# DM1092_USB.net
KiCad netlist of a schematic drawn in Altium Designer
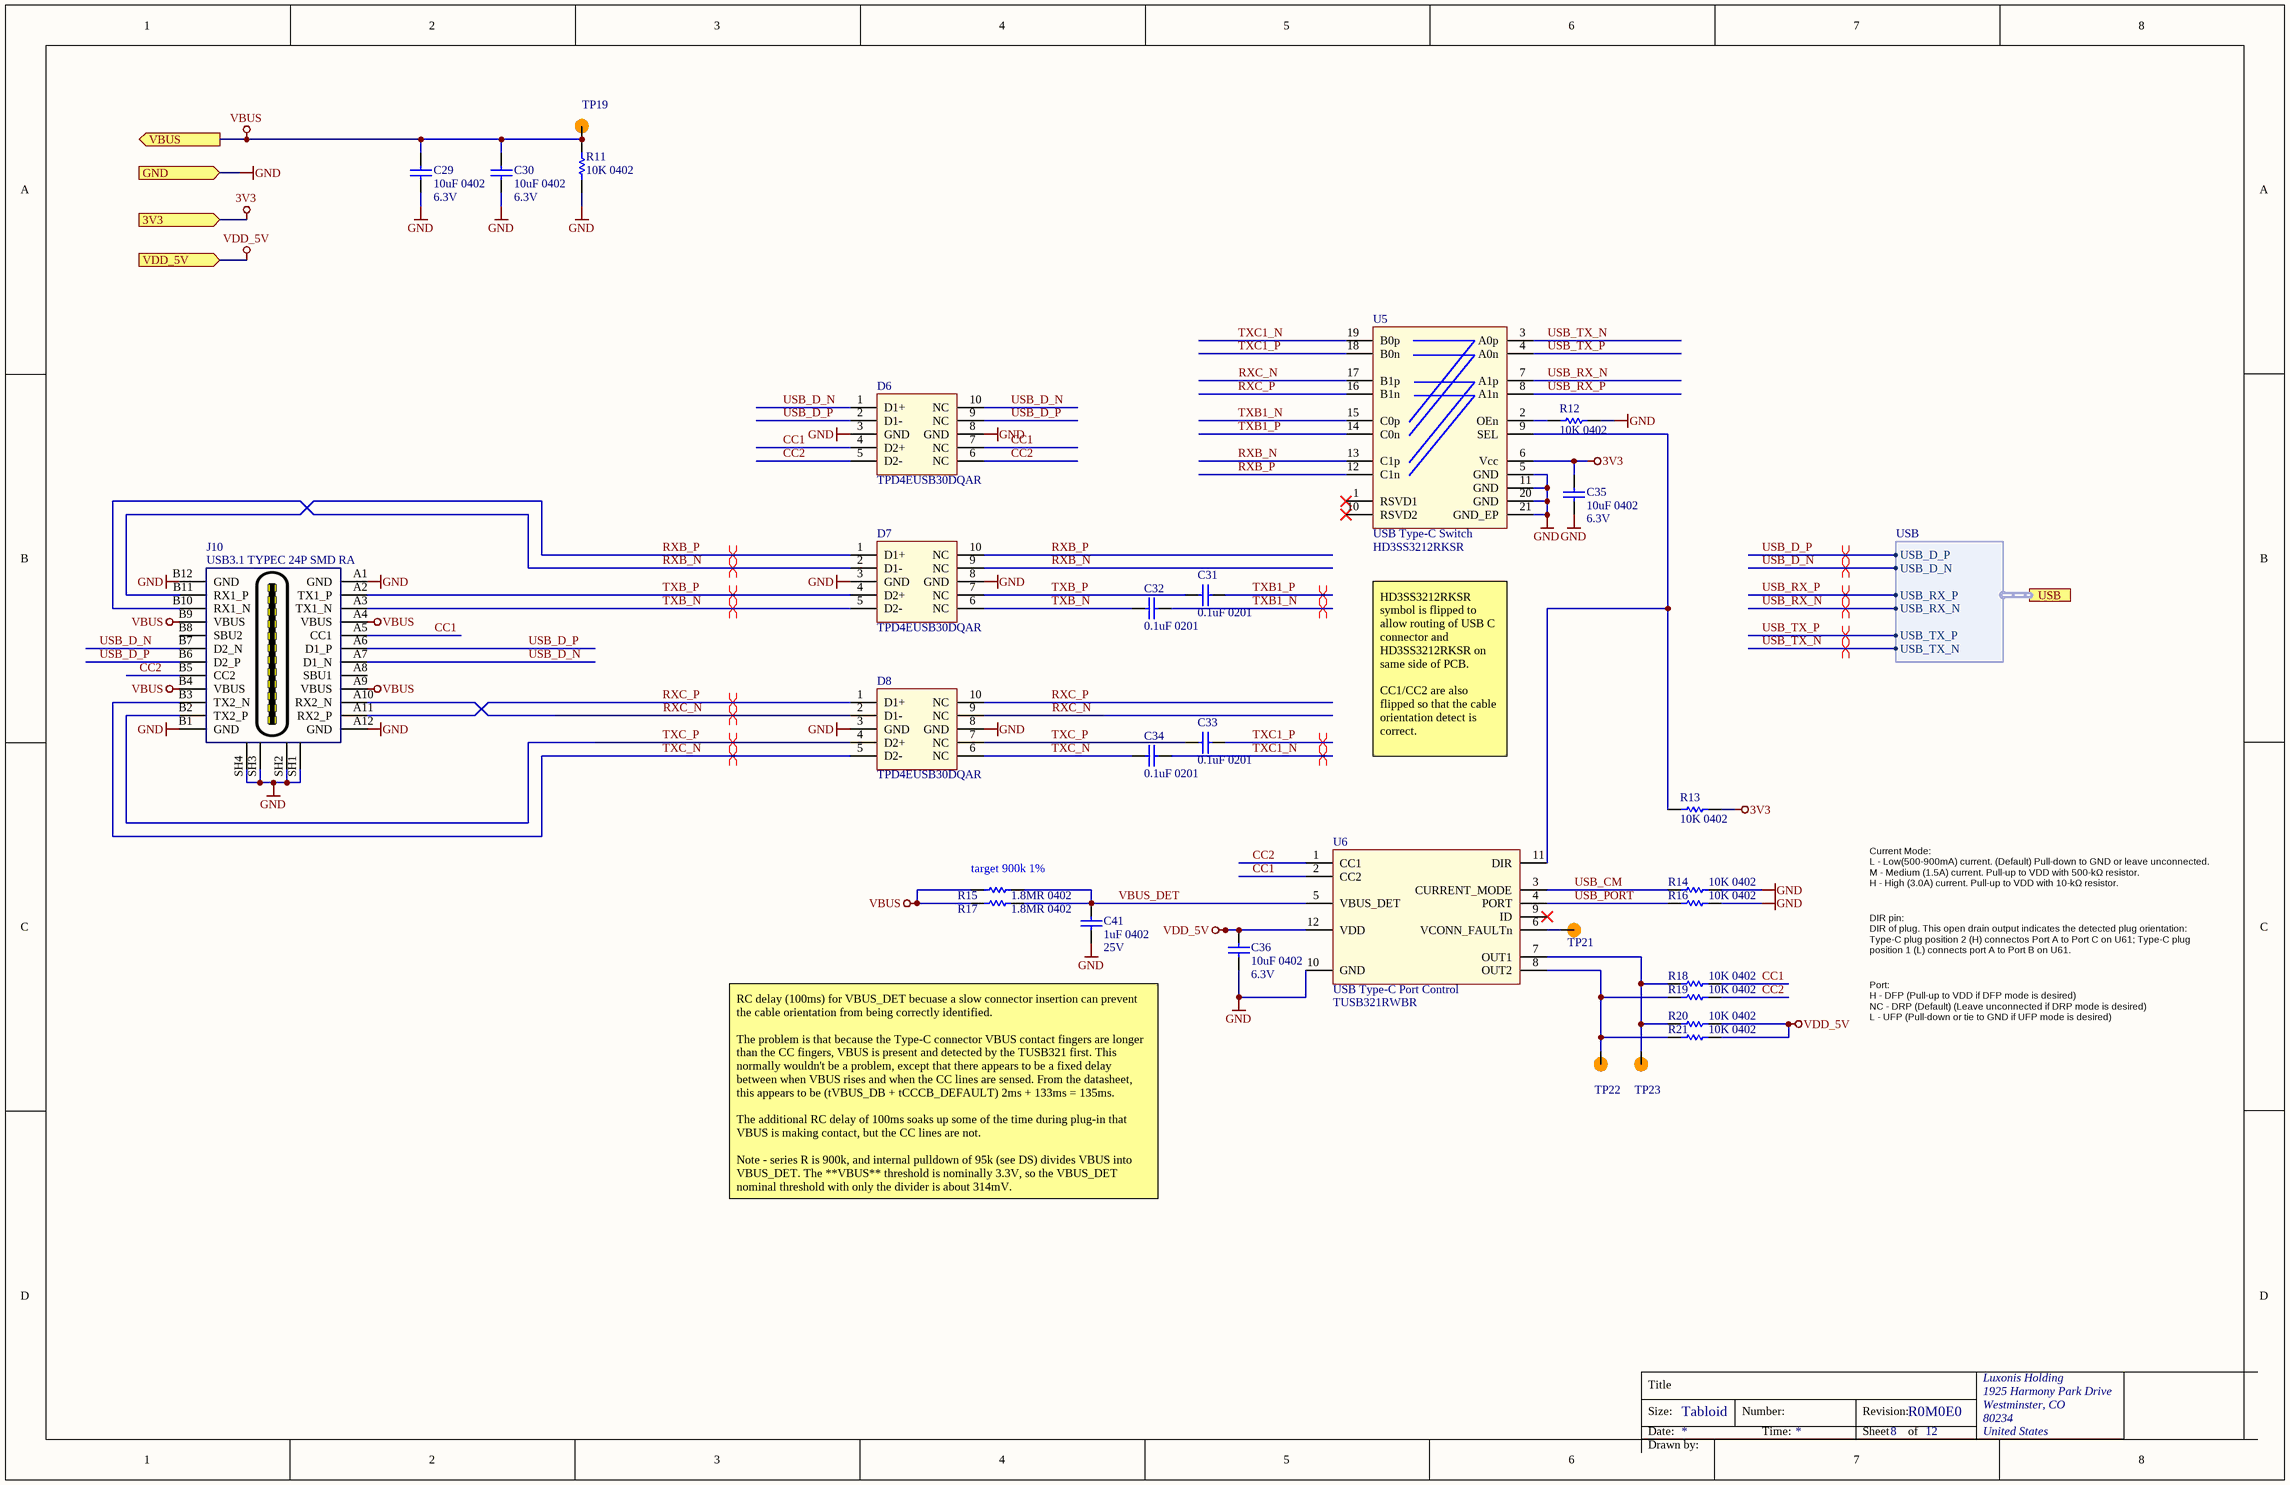
[diagram p0: DM1092_USB.SchDoc]

(export (version "E")
  (design (tool "Eeschema 10.0.6"))
  (components
    (comp (ref "C29")
      (value "10uF 0402")
      (footprint "CAP_Altium_Vault_Generic:CAPC0402(1005)70_L")
      (description "CAP CER 10UF 6.3V X5R 0402 20%")
      (fields (field (name "TOLERANCE") "20%") (field (name "VOLTAGE RATING") "6.3V"))
      (libsource (lib "LuxonisMaster") (part "GRM155R60J106ME15D"))
    )
    (comp (ref "C30")
      (value "10uF 0402")
      (footprint "CAP_Altium_Vault_Generic:CAPC0402(1005)70_L")
      (description "CAP CER 10UF 6.3V X5R 0402 20%")
      (fields (field (name "TOLERANCE") "20%") (field (name "VOLTAGE RATING") "6.3V"))
      (libsource (lib "LuxonisMaster") (part "GRM155R60J106ME15D"))
    )
    (comp (ref "C31")
      (value "0.1uF 0201")
      (footprint "CAP_Altium_Vault_Generic:CAPC0201(0603)33_L")
      (description "CAP CER 0.1UF 10V X5R 0201")
      (fields (field (name "TOLERANCE") "10%") (field (name "VOLTAGE") "10V"))
      (libsource (lib "LuxonisMaster") (part "GRM033R61A104KE15D"))
    )
    (comp (ref "C32")
      (value "0.1uF 0201")
      (footprint "CAP_Altium_Vault_Generic:CAPC0201(0603)33_L")
      (description "CAP CER 0.1UF 10V X5R 0201")
      (fields (field (name "TOLERANCE") "10%") (field (name "VOLTAGE") "10V"))
      (libsource (lib "LuxonisMaster") (part "GRM033R61A104KE15D"))
    )
    (comp (ref "C33")
      (value "0.1uF 0201")
      (footprint "CAP_Altium_Vault_Generic:CAPC0201(0603)33_L")
      (description "CAP CER 0.1UF 10V X5R 0201")
      (fields (field (name "TOLERANCE") "10%") (field (name "VOLTAGE") "10V"))
      (libsource (lib "LuxonisMaster") (part "GRM033R61A104KE15D"))
    )
    (comp (ref "C34")
      (value "0.1uF 0201")
      (footprint "CAP_Altium_Vault_Generic:CAPC0201(0603)33_L")
      (description "CAP CER 0.1UF 10V X5R 0201")
      (fields (field (name "TOLERANCE") "10%") (field (name "VOLTAGE") "10V"))
      (libsource (lib "LuxonisMaster") (part "GRM033R61A104KE15D"))
    )
    (comp (ref "C35")
      (value "10uF 0402")
      (footprint "CAP_Altium_Vault_Generic:CAPC0402(1005)70_L")
      (description "CAP CER 10UF 6.3V X5R 0402 20%")
      (fields (field (name "TOLERANCE") "20%") (field (name "VOLTAGE RATING") "6.3V"))
      (libsource (lib "LuxonisMaster") (part "GRM155R60J106ME15D"))
    )
    (comp (ref "C36")
      (value "10uF 0402")
      (footprint "CAP_Altium_Vault_Generic:CAPC0402(1005)70_L")
      (description "CAP CER 10UF 6.3V X5R 0402 20%")
      (fields (field (name "TOLERANCE") "20%") (field (name "VOLTAGE RATING") "6.3V"))
      (libsource (lib "LuxonisMaster") (part "GRM155R60J106ME15D"))
    )
    (comp (ref "C41")
      (value "1uF 0402")
      (footprint "CAP_Altium_Vault_Generic:CAPC0402(1005)70_N")
      (description "CAP CER 1UF 25V X5R 0402 10%")
      (fields
        (field (name "TOLERANCE") "10%")
        (field (name "VOLTAGE") "25V")
        (field (name "VOLTAGE RATING") "25V")
      )
      (libsource (lib "LuxonisMaster") (part "GRM155R61E105KA12D"))
    )
    (comp (ref "D6")
      (value "TPD4EUSB30DQAR")
      (footprint "LuxonisMaster:TPD4EUSB30DQAR")
      (description "TVS DIODE 5.5V 8V 10SON 8V Clamp 1A (8/20µs) Ipp Tvs Diode Surface Mount 10-USON (2.5x1)")
      (libsource (lib "LuxonisMaster") (part "TPD4EUSB30DQAR"))
    )
    (comp (ref "D7")
      (value "TPD4EUSB30DQAR")
      (footprint "LuxonisMaster:TPD4EUSB30DQAR")
      (description "TVS DIODE 5.5V 8V 10SON 8V Clamp 1A (8/20µs) Ipp Tvs Diode Surface Mount 10-USON (2.5x1)")
      (libsource (lib "LuxonisMaster") (part "TPD4EUSB30DQAR"))
    )
    (comp (ref "D8")
      (value "TPD4EUSB30DQAR")
      (footprint "LuxonisMaster:TPD4EUSB30DQAR")
      (description "TVS DIODE 5.5V 8V 10SON 8V Clamp 1A (8/20µs) Ipp Tvs Diode Surface Mount 10-USON (2.5x1)")
      (libsource (lib "LuxonisMaster") (part "TPD4EUSB30DQAR"))
    )
    (comp (ref "J10")
      (value "USB3.1 TYPEC 24P SMD RA")
      (footprint "LuxonisMaster:105450-0101")
      (description "CONN RCP USB3.1 TYPEC 24P SMD RA")
      (libsource (lib "LuxonisMaster") (part "105450-0101"))
    )
    (comp (ref "R11")
      (value "10K 0402")
      (footprint "RES_Altium_Vault_Generic:RESC0402(1005)_L")
      (fields (field (name "TOLERANCE") "1%"))
      (libsource (lib "LuxonisMaster") (part "RC0402FR-1310KL"))
    )
    (comp (ref "R12")
      (value "10K 0402")
      (footprint "RES_Altium_Vault_Generic:RESC0402(1005)_L")
      (fields (field (name "TOLERANCE") "1%"))
      (libsource (lib "LuxonisMaster") (part "RC0402FR-1310KL"))
    )
    (comp (ref "R13")
      (value "10K 0402")
      (footprint "RES_Altium_Vault_Generic:RESC0402(1005)_L")
      (fields (field (name "TOLERANCE") "1%"))
      (libsource (lib "LuxonisMaster") (part "RC0402FR-1310KL"))
    )
    (comp (ref "R14")
      (value "10K 0402")
      (footprint "RES_Altium_Vault_Generic:RESC0402(1005)_L")
      (fields (field (name "TOLERANCE") "1%"))
      (libsource (lib "LuxonisMaster") (part "RC0402FR-1310KL"))
    )
    (comp (ref "R15")
      (value "1.8MR 0402")
      (footprint "RES_Altium_Vault_Generic:RESC0402(1005)_L")
      (description "RES SMD 1.8M OHM 1% 1/16W 0402")
      (fields (field (name "TOLERANCE") "1%"))
      (libsource (lib "LuxonisMaster") (part "CRCW04021M80FKED"))
    )
    (comp (ref "R16")
      (value "10K 0402")
      (footprint "RES_Altium_Vault_Generic:RESC0402(1005)_L")
      (fields (field (name "TOLERANCE") "1%"))
      (libsource (lib "LuxonisMaster") (part "RC0402FR-1310KL"))
    )
    (comp (ref "R17")
      (value "1.8MR 0402")
      (footprint "RES_Altium_Vault_Generic:RESC0402(1005)_L")
      (description "RES SMD 1.8M OHM 1% 1/16W 0402")
      (fields (field (name "TOLERANCE") "1%"))
      (libsource (lib "LuxonisMaster") (part "CRCW04021M80FKED"))
    )
    (comp (ref "R18")
      (value "10K 0402")
      (footprint "RES_Altium_Vault_Generic:RESC0402(1005)_L")
      (fields (field (name "TOLERANCE") "1%"))
      (libsource (lib "LuxonisMaster") (part "RC0402FR-1310KL"))
    )
    (comp (ref "R19")
      (value "10K 0402")
      (footprint "RES_Altium_Vault_Generic:RESC0402(1005)_L")
      (fields (field (name "TOLERANCE") "1%"))
      (libsource (lib "LuxonisMaster") (part "RC0402FR-1310KL"))
    )
    (comp (ref "R20")
      (value "10K 0402")
      (footprint "RES_Altium_Vault_Generic:RESC0402(1005)_L")
      (fields (field (name "TOLERANCE") "1%"))
      (libsource (lib "LuxonisMaster") (part "RC0402FR-1310KL"))
    )
    (comp (ref "R21")
      (value "10K 0402")
      (footprint "RES_Altium_Vault_Generic:RESC0402(1005)_L")
      (fields (field (name "TOLERANCE") "1%"))
      (libsource (lib "LuxonisMaster") (part "RC0402FR-1310KL"))
    )
    (comp (ref "TP19")
      (value "TP100_200_NS")
      (footprint "LuxonisMaster:TP100_200_NS")
      (libsource (lib "LuxonisMaster") (part "TEST_POINT"))
    )
    (comp (ref "TP21")
      (value "TP075_150_NS")
      (footprint "LuxonisMaster:TP075_150_NS")
      (libsource (lib "LuxonisMaster") (part "TEST_POINT"))
    )
    (comp (ref "TP22")
      (value "TP075_150_NS")
      (footprint "LuxonisMaster:TP075_150_NS")
      (libsource (lib "LuxonisMaster") (part "TEST_POINT"))
    )
    (comp (ref "TP23")
      (value "TP075_150_NS")
      (footprint "LuxonisMaster:TP075_150_NS")
      (libsource (lib "LuxonisMaster") (part "TEST_POINT"))
    )
    (comp (ref "U5")
      (value "USB Type-C Switch")
      (footprint "LuxonisMaster:HD3SS3212RKSR")
      (description "IC MUX 2:1 8 OHM 20VQFN")
      (fields (field (name "MANUFACTURER PART NUMBER 1") "HD3SS3212RKSR"))
      (libsource (lib "LuxonisMaster") (part "HD3SS3212RKSR"))
    )
    (comp (ref "U6")
      (value "USB Type-C Port Control")
      (footprint "LuxonisMaster:TUSB321RWBR")
      (description "IC USB PORT CONTROL TYPE-C 12X2Q")
      (fields (field (name "MANUFACTURER PART NUMBER 1") "TUSB321RWBR"))
      (libsource (lib "LuxonisMaster") (part "TUSB321RWBR"))
    )
  )
  (nets
    (net (code "2") (name "/CC1") (class "Default")
      (node (ref "D6") (pin "4") (pinfunction "D2+_4") (pintype "passive"))
      (node (ref "D6") (pin "7") (pinfunction "NC_7") (pintype "passive"))
      (node (ref "J10") (pin "A5") (pinfunction "CC1_A5") (pintype "passive"))
      (node (ref "R18") (pin "2") (pinfunction "2_2") (pintype "passive"))
      (node (ref "U6") (pin "2") (pinfunction "CC2_2") (pintype "passive"))
    )
    (net (code "3") (name "/CC2") (class "Default")
      (node (ref "D6") (pin "5") (pinfunction "D2-_5") (pintype "passive"))
      (node (ref "D6") (pin "6") (pinfunction "NC_6") (pintype "passive"))
      (node (ref "J10") (pin "B5") (pinfunction "CC2_B5") (pintype "passive"))
      (node (ref "R19") (pin "2") (pinfunction "2_2") (pintype "passive"))
      (node (ref "U6") (pin "1") (pinfunction "CC1_1") (pintype "passive"))
    )
    (net (code "4") (name "/RXB_N") (class "Default")
      (node (ref "D7") (pin "2") (pinfunction "D1-_2") (pintype "passive"))
      (node (ref "D7") (pin "9") (pinfunction "NC_9") (pintype "passive"))
      (node (ref "J10") (pin "B10") (pinfunction "RX1_N_B10") (pintype "passive"))
      (node (ref "U5") (pin "13") (pinfunction "C1p_13") (pintype "passive"))
    )
    (net (code "5") (name "/RXB_P") (class "Default")
      (node (ref "D7") (pin "1") (pinfunction "D1+_1") (pintype "passive"))
      (node (ref "D7") (pin "10") (pinfunction "NC_10") (pintype "passive"))
      (node (ref "J10") (pin "B11") (pinfunction "RX1_P_B11") (pintype "passive"))
      (node (ref "U5") (pin "12") (pinfunction "C1n_12") (pintype "passive"))
    )
    (net (code "6") (name "/RXC_N") (class "Default")
      (node (ref "D8") (pin "2") (pinfunction "D1-_2") (pintype "passive"))
      (node (ref "D8") (pin "9") (pinfunction "NC_9") (pintype "passive"))
      (node (ref "J10") (pin "A10") (pinfunction "RX2_N_A10") (pintype "passive"))
      (node (ref "U5") (pin "17") (pinfunction "B1p_17") (pintype "passive"))
    )
    (net (code "7") (name "/RXC_P") (class "Default")
      (node (ref "D8") (pin "1") (pinfunction "D1+_1") (pintype "passive"))
      (node (ref "D8") (pin "10") (pinfunction "NC_10") (pintype "passive"))
      (node (ref "J10") (pin "A11") (pinfunction "RX2_P_A11") (pintype "passive"))
      (node (ref "U5") (pin "16") (pinfunction "B1n_16") (pintype "passive"))
    )
    (net (code "8") (name "/TXB1_N") (class "Default")
      (node (ref "C32") (pin "2") (pinfunction "2_2") (pintype "passive"))
      (node (ref "U5") (pin "15") (pinfunction "C0p_15") (pintype "passive"))
    )
    (net (code "9") (name "/TXB1_P") (class "Default")
      (node (ref "C31") (pin "2") (pinfunction "2_2") (pintype "passive"))
      (node (ref "U5") (pin "14") (pinfunction "C0n_14") (pintype "passive"))
    )
    (net (code "10") (name "/TXB_N") (class "Default")
      (node (ref "C32") (pin "1") (pinfunction "1_1") (pintype "passive"))
      (node (ref "D7") (pin "5") (pinfunction "D2-_5") (pintype "passive"))
      (node (ref "D7") (pin "6") (pinfunction "NC_6") (pintype "passive"))
      (node (ref "J10") (pin "A3") (pinfunction "TX1_N_A3") (pintype "passive"))
    )
    (net (code "11") (name "/TXB_P") (class "Default")
      (node (ref "C31") (pin "1") (pinfunction "1_1") (pintype "passive"))
      (node (ref "D7") (pin "4") (pinfunction "D2+_4") (pintype "passive"))
      (node (ref "D7") (pin "7") (pinfunction "NC_7") (pintype "passive"))
      (node (ref "J10") (pin "A2") (pinfunction "TX1_P_A2") (pintype "passive"))
    )
    (net (code "12") (name "/TXC1_N") (class "Default")
      (node (ref "C34") (pin "2") (pinfunction "2_2") (pintype "passive"))
      (node (ref "U5") (pin "19") (pinfunction "B0p_19") (pintype "passive"))
    )
    (net (code "13") (name "/TXC1_P") (class "Default")
      (node (ref "C33") (pin "2") (pinfunction "2_2") (pintype "passive"))
      (node (ref "U5") (pin "18") (pinfunction "B0n_18") (pintype "passive"))
    )
    (net (code "14") (name "/TXC_N") (class "Default")
      (node (ref "C34") (pin "1") (pinfunction "1_1") (pintype "passive"))
      (node (ref "D8") (pin "5") (pinfunction "D2-_5") (pintype "passive"))
      (node (ref "D8") (pin "6") (pinfunction "NC_6") (pintype "passive"))
      (node (ref "J10") (pin "B3") (pinfunction "TX2_N_B3") (pintype "passive"))
    )
    (net (code "15") (name "/TXC_P") (class "Default")
      (node (ref "C33") (pin "1") (pinfunction "1_1") (pintype "passive"))
      (node (ref "D8") (pin "4") (pinfunction "D2+_4") (pintype "passive"))
      (node (ref "D8") (pin "7") (pinfunction "NC_7") (pintype "passive"))
      (node (ref "J10") (pin "B2") (pinfunction "TX2_P_B2") (pintype "passive"))
    )
    (net (code "16") (name "/USB_CM") (class "Default")
      (node (ref "R14") (pin "1") (pinfunction "1_1") (pintype "passive"))
      (node (ref "U6") (pin "3") (pinfunction "CURRENT_MODE_3") (pintype "passive"))
    )
    (net (code "17") (name "/USB_D_N") (class "Default")
      (node (ref "D6") (pin "1") (pinfunction "D1+_1") (pintype "passive"))
      (node (ref "D6") (pin "10") (pinfunction "NC_10") (pintype "passive"))
      (node (ref "J10") (pin "A7") (pinfunction "D1_N_A7") (pintype "passive"))
      (node (ref "J10") (pin "B7") (pinfunction "D2_N_B7") (pintype "passive"))
    )
    (net (code "18") (name "/USB_D_P") (class "Default")
      (node (ref "D6") (pin "2") (pinfunction "D1-_2") (pintype "passive"))
      (node (ref "D6") (pin "9") (pinfunction "NC_9") (pintype "passive"))
      (node (ref "J10") (pin "A6") (pinfunction "D1_P_A6") (pintype "passive"))
      (node (ref "J10") (pin "B6") (pinfunction "D2_P_B6") (pintype "passive"))
    )
    (net (code "19") (name "/USB_PORT") (class "Default")
      (node (ref "R16") (pin "1") (pinfunction "1_1") (pintype "passive"))
      (node (ref "U6") (pin "4") (pinfunction "PORT_4") (pintype "passive"))
    )
    (net (code "20") (name "/USB_RX_N") (class "Default")
      (node (ref "U5") (pin "7") (pinfunction "A1p_7") (pintype "passive"))
    )
    (net (code "21") (name "/USB_RX_P") (class "Default")
      (node (ref "U5") (pin "8") (pinfunction "A1n_8") (pintype "passive"))
    )
    (net (code "22") (name "/USB_TX_N") (class "Default")
      (node (ref "U5") (pin "3") (pinfunction "A0p_3") (pintype "passive"))
    )
    (net (code "23") (name "/USB_TX_P") (class "Default")
      (node (ref "U5") (pin "4") (pinfunction "A0n_4") (pintype "passive"))
    )
    (net (code "24") (name "/VBUS_DET") (class "Default")
      (node (ref "C41") (pin "2") (pinfunction "2_2") (pintype "passive"))
      (node (ref "R15") (pin "2") (pinfunction "2_2") (pintype "passive"))
      (node (ref "R17") (pin "2") (pinfunction "2_2") (pintype "passive"))
      (node (ref "U6") (pin "5") (pinfunction "VBUS_DET_5") (pintype "passive"))
    )
    (net (code "26") (name "3V3") (class "Default")
      (node (ref "C35") (pin "2") (pinfunction "2_2") (pintype "passive"))
      (node (ref "R13") (pin "2") (pinfunction "2_2") (pintype "passive"))
      (node (ref "U5") (pin "6") (pinfunction "Vcc_6") (pintype "passive"))
    )
    (net (code "27") (name "GND") (class "Default")
      (node (ref "C29") (pin "1") (pinfunction "1_1") (pintype "passive"))
      (node (ref "C30") (pin "1") (pinfunction "1_1") (pintype "passive"))
      (node (ref "C35") (pin "1") (pinfunction "1_1") (pintype "passive"))
      (node (ref "C36") (pin "1") (pinfunction "1_1") (pintype "passive"))
      (node (ref "C41") (pin "1") (pinfunction "1_1") (pintype "passive"))
      (node (ref "D6") (pin "3") (pinfunction "GND_3") (pintype "passive"))
      (node (ref "D6") (pin "8") (pinfunction "GND_8") (pintype "passive"))
      (node (ref "D7") (pin "3") (pinfunction "GND_3") (pintype "passive"))
      (node (ref "D7") (pin "8") (pinfunction "GND_8") (pintype "passive"))
      (node (ref "D8") (pin "3") (pinfunction "GND_3") (pintype "passive"))
      (node (ref "D8") (pin "8") (pinfunction "GND_8") (pintype "passive"))
      (node (ref "J10") (pin "A1") (pinfunction "GND_A1") (pintype "passive"))
      (node (ref "J10") (pin "A12") (pinfunction "GND_A12") (pintype "passive"))
      (node (ref "J10") (pin "B1") (pinfunction "GND_B1") (pintype "passive"))
      (node (ref "J10") (pin "B12") (pinfunction "GND_B12") (pintype "passive"))
      (node (ref "J10") (pin "SH1") (pinfunction "SH_SH1") (pintype "passive"))
      (node (ref "J10") (pin "SH2") (pinfunction "SH_SH2") (pintype "passive"))
      (node (ref "J10") (pin "SH3") (pinfunction "SH_SH3") (pintype "passive"))
      (node (ref "J10") (pin "SH4") (pinfunction "SH_SH4") (pintype "passive"))
      (node (ref "R11") (pin "1") (pinfunction "1_1") (pintype "passive"))
      (node (ref "R12") (pin "2") (pinfunction "2_2") (pintype "passive"))
      (node (ref "R14") (pin "2") (pinfunction "2_2") (pintype "passive"))
      (node (ref "R16") (pin "2") (pinfunction "2_2") (pintype "passive"))
      (node (ref "U5") (pin "11") (pinfunction "GND_11") (pintype "passive"))
      (node (ref "U5") (pin "20") (pinfunction "GND_20") (pintype "passive"))
      (node (ref "U5") (pin "21") (pinfunction "GND_EP_21") (pintype "passive"))
      (node (ref "U5") (pin "5") (pinfunction "GND_5") (pintype "passive"))
      (node (ref "U6") (pin "10") (pinfunction "GND_10") (pintype "passive"))
    )
    (net (code "28") (name "Net-(U5-OEn)") (class "Default")
      (node (ref "R12") (pin "1") (pinfunction "1_1") (pintype "passive"))
      (node (ref "U5") (pin "2") (pinfunction "OEn_2") (pintype "passive"))
    )
    (net (code "29") (name "Net-(U5-SEL)") (class "Default")
      (node (ref "R13") (pin "1") (pinfunction "1_1") (pintype "passive"))
      (node (ref "U5") (pin "9") (pinfunction "SEL_9") (pintype "passive"))
      (node (ref "U6") (pin "11") (pinfunction "DIR_11") (pintype "passive"))
    )
    (net (code "30") (name "Net-(U6-OUT1)") (class "Default")
      (node (ref "R18") (pin "1") (pinfunction "1_1") (pintype "passive"))
      (node (ref "R20") (pin "1") (pinfunction "1_1") (pintype "passive"))
      (node (ref "TP23") (pin "1") (pintype "passive"))
      (node (ref "U6") (pin "7") (pinfunction "OUT1_7") (pintype "passive"))
    )
    (net (code "31") (name "Net-(U6-OUT2)") (class "Default")
      (node (ref "R19") (pin "1") (pinfunction "1_1") (pintype "passive"))
      (node (ref "R21") (pin "1") (pinfunction "1_1") (pintype "passive"))
      (node (ref "TP22") (pin "1") (pintype "passive"))
      (node (ref "U6") (pin "8") (pinfunction "OUT2_8") (pintype "passive"))
    )
    (net (code "32") (name "Net-(U6-VCONN_FAULTn)") (class "Default")
      (node (ref "TP21") (pin "1") (pintype "passive"))
      (node (ref "U6") (pin "6") (pinfunction "VCONN_FAULTn_6") (pintype "passive"))
    )
    (net (code "33") (name "VBUS") (class "Default")
      (node (ref "C29") (pin "2") (pinfunction "2_2") (pintype "passive"))
      (node (ref "C30") (pin "2") (pinfunction "2_2") (pintype "passive"))
      (node (ref "J10") (pin "A4") (pinfunction "VBUS_A4") (pintype "passive"))
      (node (ref "J10") (pin "A9") (pinfunction "VBUS_A9") (pintype "passive"))
      (node (ref "J10") (pin "B4") (pinfunction "VBUS_B4") (pintype "passive"))
      (node (ref "J10") (pin "B9") (pinfunction "VBUS_B9") (pintype "passive"))
      (node (ref "R11") (pin "2") (pinfunction "2_2") (pintype "passive"))
      (node (ref "R15") (pin "1") (pinfunction "1_1") (pintype "passive"))
      (node (ref "R17") (pin "1") (pinfunction "1_1") (pintype "passive"))
      (node (ref "TP19") (pin "1") (pintype "passive"))
    )
    (net (code "34") (name "VDD_5V") (class "Default")
      (node (ref "C36") (pin "2") (pinfunction "2_2") (pintype "passive"))
      (node (ref "R20") (pin "2") (pinfunction "2_2") (pintype "passive"))
      (node (ref "R21") (pin "2") (pinfunction "2_2") (pintype "passive"))
      (node (ref "U6") (pin "12") (pinfunction "VDD_12") (pintype "passive"))
    )
    (net (code "35") (name "unconnected-(J10-SBU1-PadA8)") (class "Default")
      (node (ref "J10") (pin "A8") (pinfunction "SBU1_A8") (pintype "passive"))
    )
    (net (code "36") (name "unconnected-(J10-SBU2-PadB8)") (class "Default")
      (node (ref "J10") (pin "B8") (pinfunction "SBU2_B8") (pintype "passive"))
    )
    (net (code "37") (name "unconnected-(U5-RSVD1-Pad1)") (class "Default")
      (node (ref "U5") (pin "1") (pinfunction "RSVD1_1") (pintype "passive+no_connect"))
    )
    (net (code "38") (name "unconnected-(U5-RSVD2-Pad10)") (class "Default")
      (node (ref "U5") (pin "10") (pinfunction "RSVD2_10") (pintype "passive+no_connect"))
    )
    (net (code "39") (name "unconnected-(U6-ID-Pad9)") (class "Default")
      (node (ref "U6") (pin "9") (pinfunction "ID_9") (pintype "passive+no_connect"))
    )
  )
)
